# BW1097_Power_Supply.net
KiCad netlist of a schematic drawn in Altium Designer
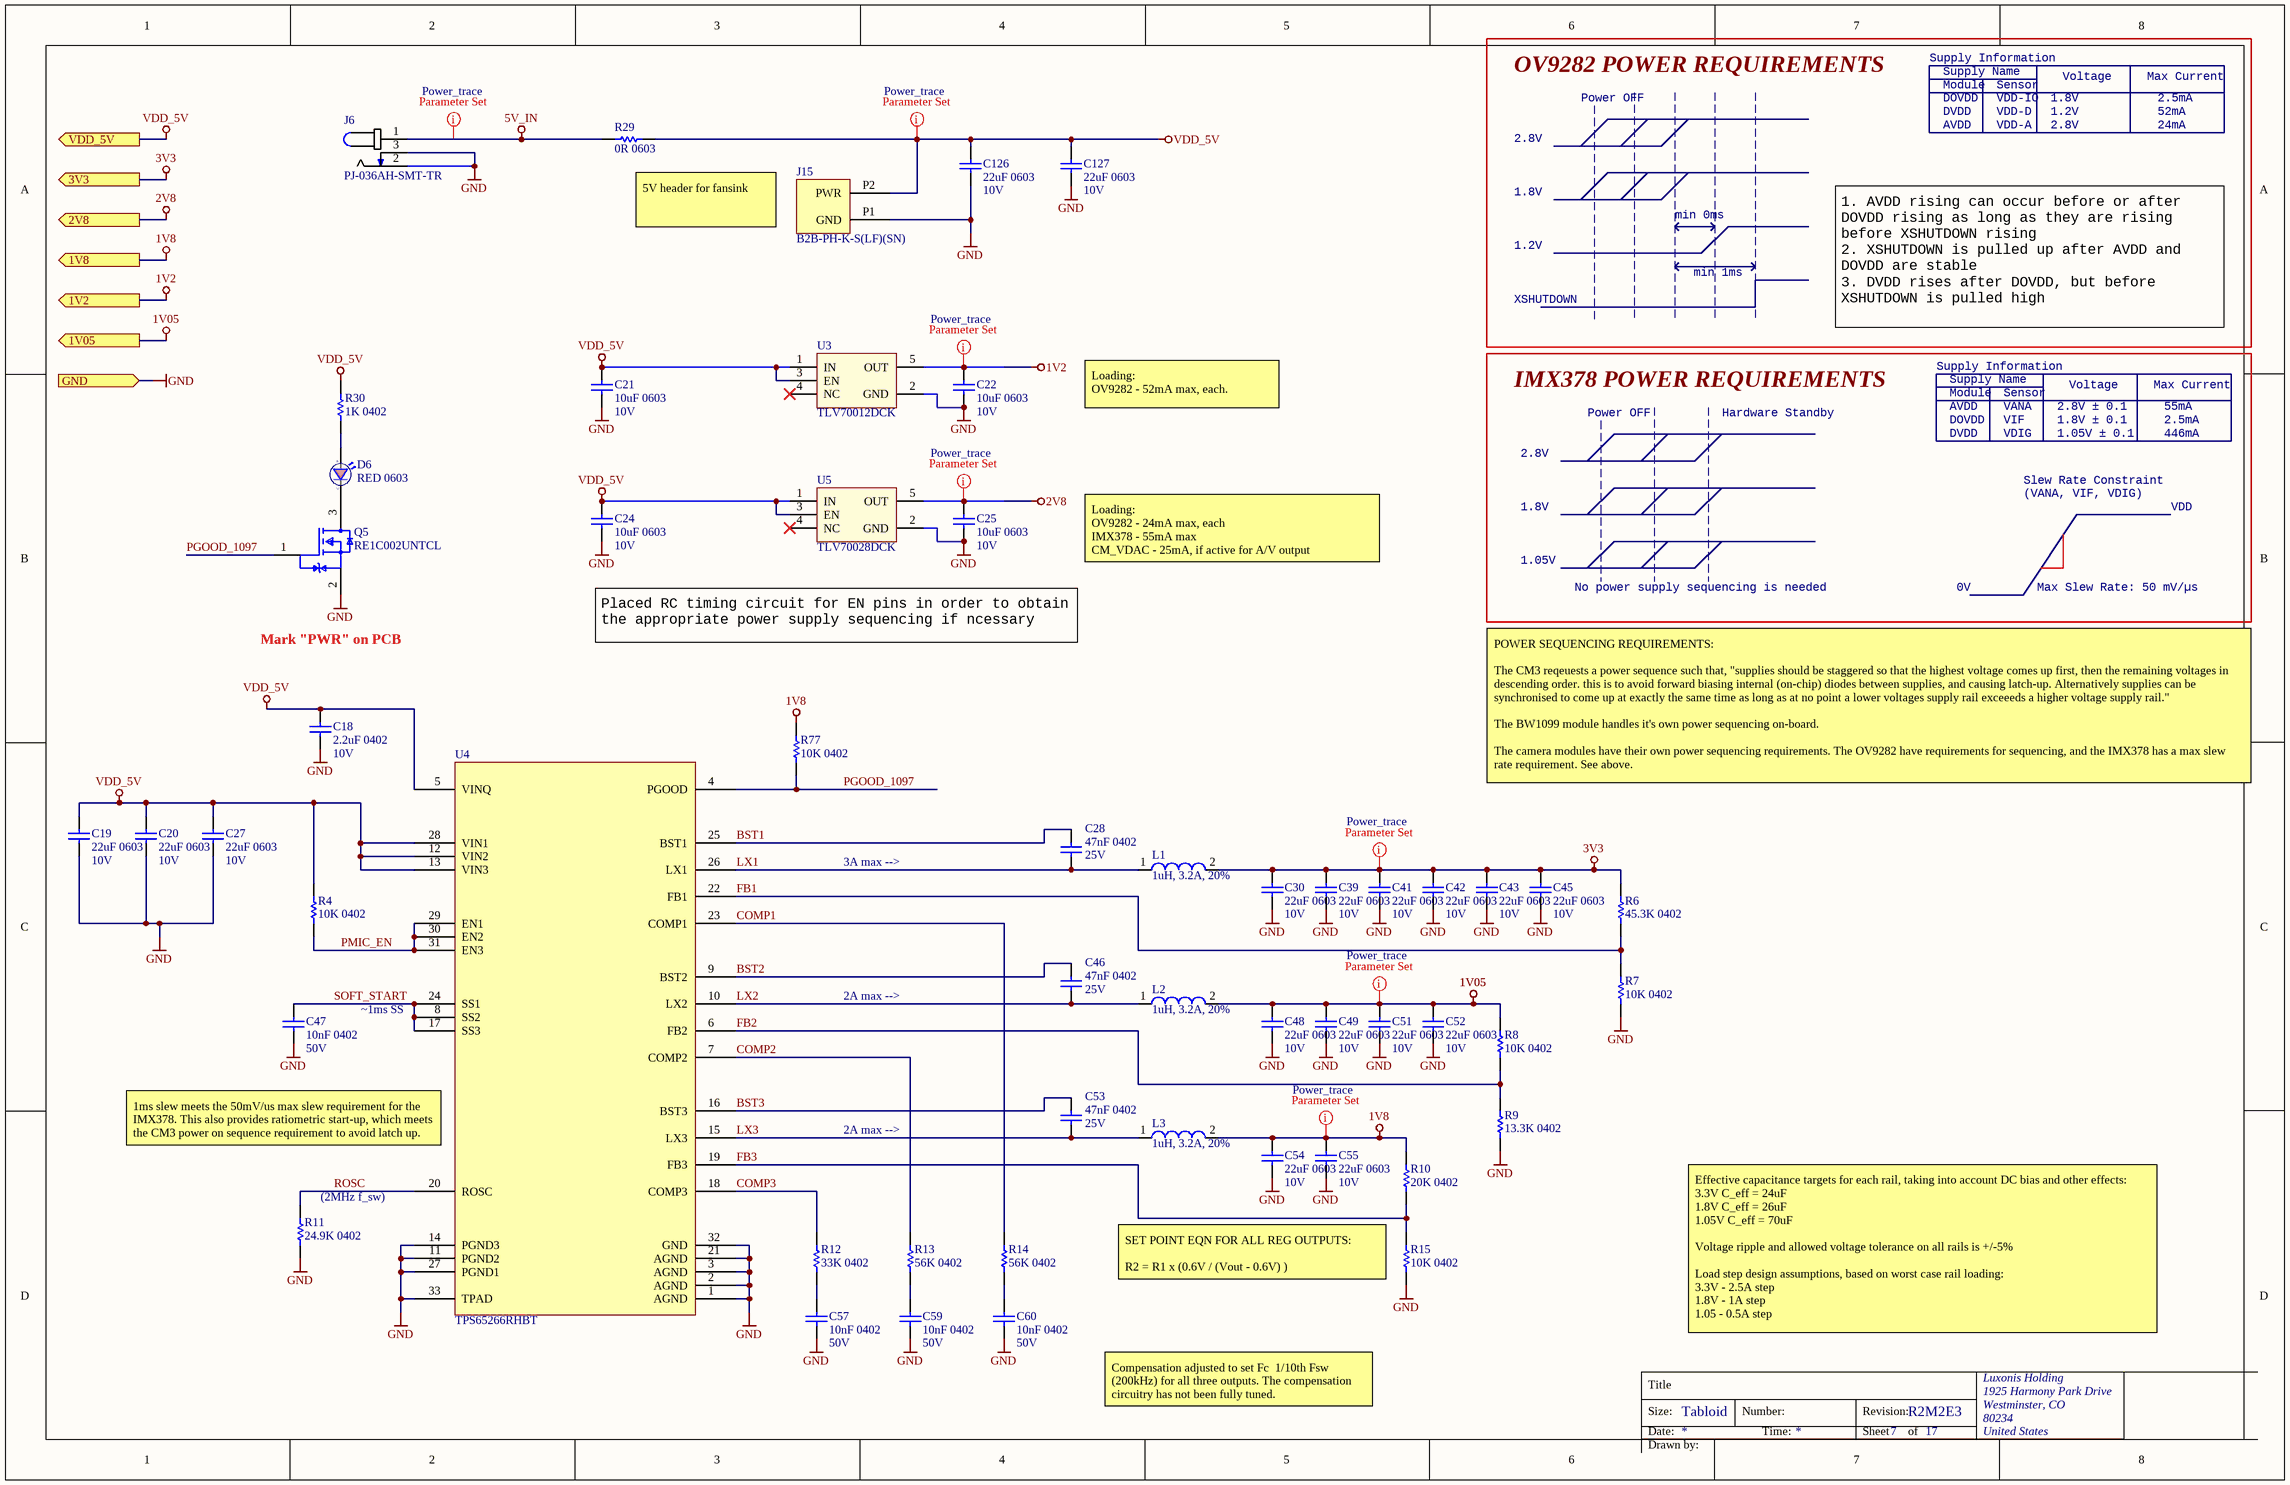
[diagram p0: BW1097_Power_Supply.SchDoc]

(export (version "E")
  (design (tool "Eeschema 10.0.6"))
  (components
    (comp (ref "C18")
      (value "2.2uF 0402")
      (footprint "CAP_Altium_Vault_Generic:CAPC0402(1005)70_N")
      (description "CAP CER 2.2UF 10V X5R 0402 10%")
      (fields (field (name "TOLERANCE") "10%") (field (name "VOLTAGE RATING") "10V"))
      (libsource (lib "LuxonisMaster") (part "GRM155R61A225KE95D"))
    )
    (comp (ref "C19")
      (value "22uF 0603")
      (footprint "CAP_Altium_Vault_Generic:CAPC0603(1608)100_N")
      (description "CAP CER 22UF 10V X5R 0603 20%")
      (fields (field (name "TOLERANCE") "20%") (field (name "VOLTAGE RATING") "10V"))
      (libsource (lib "LuxonisMaster") (part "GRM188R61A226ME15D"))
    )
    (comp (ref "C20")
      (value "22uF 0603")
      (footprint "CAP_Altium_Vault_Generic:CAPC0603(1608)100_N")
      (description "CAP CER 22UF 10V X5R 0603 20%")
      (fields (field (name "TOLERANCE") "20%") (field (name "VOLTAGE RATING") "10V"))
      (libsource (lib "LuxonisMaster") (part "GRM188R61A226ME15D"))
    )
    (comp (ref "C21")
      (value "10uF 0603")
      (footprint "CAP_Altium_Vault_Generic:CAPC0603(1608)100_N")
      (description "CAP CER 10UF 10V X5R 0603 20%")
      (fields (field (name "TOLERANCE") "20%") (field (name "VOLTAGE RATING") "10V"))
      (libsource (lib "LuxonisMaster") (part "GRM188R61A106ME69D"))
    )
    (comp (ref "C22")
      (value "10uF 0603")
      (footprint "CAP_Altium_Vault_Generic:CAPC0603(1608)100_N")
      (description "CAP CER 10UF 10V X5R 0603 20%")
      (fields (field (name "TOLERANCE") "20%") (field (name "VOLTAGE RATING") "10V"))
      (libsource (lib "LuxonisMaster") (part "GRM188R61A106ME69D"))
    )
    (comp (ref "C24")
      (value "10uF 0603")
      (footprint "CAP_Altium_Vault_Generic:CAPC0603(1608)100_N")
      (description "CAP CER 10UF 10V X5R 0603 20%")
      (fields (field (name "TOLERANCE") "20%") (field (name "VOLTAGE RATING") "10V"))
      (libsource (lib "LuxonisMaster") (part "GRM188R61A106ME69D"))
    )
    (comp (ref "C25")
      (value "10uF 0603")
      (footprint "CAP_Altium_Vault_Generic:CAPC0603(1608)100_N")
      (description "CAP CER 10UF 10V X5R 0603 20%")
      (fields (field (name "TOLERANCE") "20%") (field (name "VOLTAGE RATING") "10V"))
      (libsource (lib "LuxonisMaster") (part "GRM188R61A106ME69D"))
    )
    (comp (ref "C27")
      (value "22uF 0603")
      (footprint "CAP_Altium_Vault_Generic:CAPC0603(1608)100_N")
      (description "CAP CER 22UF 10V X5R 0603 20%")
      (fields (field (name "TOLERANCE") "20%") (field (name "VOLTAGE RATING") "10V"))
      (libsource (lib "LuxonisMaster") (part "GRM188R61A226ME15D"))
    )
    (comp (ref "C28")
      (value "47nF 0402")
      (footprint "CAP_Altium_Vault_Generic:CAPC0402(1005)70_N")
      (description "CAP CER 0.047UF 25V X7R 0402 10%")
      (fields
        (field (name "MANUFACTURER") "Murata")
        (field (name "MANUFACTURER PART NUMBER") "GRM155R71E473KA88D")
        (field (name "VOLTAGE") "25V")
      )
      (libsource (lib "LuxonisMaster") (part "GRM155R71E473KA88D"))
    )
    (comp (ref "C30")
      (value "22uF 0603")
      (footprint "CAP_Altium_Vault_Generic:CAPC0603(1608)100_N")
      (description "CAP CER 22UF 10V X5R 0603 20%")
      (fields (field (name "TOLERANCE") "20%") (field (name "VOLTAGE RATING") "10V"))
      (libsource (lib "LuxonisMaster") (part "GRM188R61A226ME15D"))
    )
    (comp (ref "C39")
      (value "22uF 0603")
      (footprint "CAP_Altium_Vault_Generic:CAPC0603(1608)100_N")
      (description "CAP CER 22UF 10V X5R 0603 20%")
      (fields (field (name "TOLERANCE") "20%") (field (name "VOLTAGE RATING") "10V"))
      (libsource (lib "LuxonisMaster") (part "GRM188R61A226ME15D"))
    )
    (comp (ref "C41")
      (value "22uF 0603")
      (footprint "CAP_Altium_Vault_Generic:CAPC0603(1608)100_N")
      (description "CAP CER 22UF 10V X5R 0603 20%")
      (fields (field (name "TOLERANCE") "20%") (field (name "VOLTAGE RATING") "10V"))
      (libsource (lib "LuxonisMaster") (part "GRM188R61A226ME15D"))
    )
    (comp (ref "C42")
      (value "22uF 0603")
      (footprint "CAP_Altium_Vault_Generic:CAPC0603(1608)100_N")
      (description "CAP CER 22UF 10V X5R 0603 20%")
      (fields (field (name "TOLERANCE") "20%") (field (name "VOLTAGE RATING") "10V"))
      (libsource (lib "LuxonisMaster") (part "GRM188R61A226ME15D"))
    )
    (comp (ref "C43")
      (value "22uF 0603")
      (footprint "CAP_Altium_Vault_Generic:CAPC0603(1608)100_N")
      (description "CAP CER 22UF 10V X5R 0603 20%")
      (fields (field (name "TOLERANCE") "20%") (field (name "VOLTAGE RATING") "10V"))
      (libsource (lib "LuxonisMaster") (part "GRM188R61A226ME15D"))
    )
    (comp (ref "C45")
      (value "22uF 0603")
      (footprint "CAP_Altium_Vault_Generic:CAPC0603(1608)100_N")
      (description "CAP CER 22UF 10V X5R 0603 20%")
      (fields (field (name "TOLERANCE") "20%") (field (name "VOLTAGE RATING") "10V"))
      (libsource (lib "LuxonisMaster") (part "GRM188R61A226ME15D"))
    )
    (comp (ref "C46")
      (value "47nF 0402")
      (footprint "CAP_Altium_Vault_Generic:CAPC0402(1005)70_N")
      (description "CAP CER 0.047UF 25V X7R 0402 10%")
      (fields
        (field (name "MANUFACTURER") "Murata")
        (field (name "MANUFACTURER PART NUMBER") "GRM155R71E473KA88D")
        (field (name "VOLTAGE") "25V")
      )
      (libsource (lib "LuxonisMaster") (part "GRM155R71E473KA88D"))
    )
    (comp (ref "C47")
      (value "10nF 0402")
      (footprint "CAP_Altium_Vault_Generic:CAPC0402(1005)60_N")
      (description "CAP CER 10000PF 50V X7R 0402")
      (fields
        (field (name "TOLERANCE") "10%")
        (field (name "VOLTAGE") "25V")
        (field (name "VOLTAGE RATING") "50V")
      )
      (libsource (lib "LuxonisMaster") (part "GRM155R71H103KA88D"))
    )
    (comp (ref "C48")
      (value "22uF 0603")
      (footprint "CAP_Altium_Vault_Generic:CAPC0603(1608)100_N")
      (description "CAP CER 22UF 10V X5R 0603 20%")
      (fields (field (name "TOLERANCE") "20%") (field (name "VOLTAGE RATING") "10V"))
      (libsource (lib "LuxonisMaster") (part "GRM188R61A226ME15D"))
    )
    (comp (ref "C49")
      (value "22uF 0603")
      (footprint "CAP_Altium_Vault_Generic:CAPC0603(1608)100_N")
      (description "CAP CER 22UF 10V X5R 0603 20%")
      (fields (field (name "TOLERANCE") "20%") (field (name "VOLTAGE RATING") "10V"))
      (libsource (lib "LuxonisMaster") (part "GRM188R61A226ME15D"))
    )
    (comp (ref "C51")
      (value "22uF 0603")
      (footprint "CAP_Altium_Vault_Generic:CAPC0603(1608)100_N")
      (description "CAP CER 22UF 10V X5R 0603 20%")
      (fields (field (name "TOLERANCE") "20%") (field (name "VOLTAGE RATING") "10V"))
      (libsource (lib "LuxonisMaster") (part "GRM188R61A226ME15D"))
    )
    (comp (ref "C52")
      (value "22uF 0603")
      (footprint "CAP_Altium_Vault_Generic:CAPC0603(1608)100_N")
      (description "CAP CER 22UF 10V X5R 0603 20%")
      (fields (field (name "TOLERANCE") "20%") (field (name "VOLTAGE RATING") "10V"))
      (libsource (lib "LuxonisMaster") (part "GRM188R61A226ME15D"))
    )
    (comp (ref "C53")
      (value "47nF 0402")
      (footprint "CAP_Altium_Vault_Generic:CAPC0402(1005)70_N")
      (description "CAP CER 0.047UF 25V X7R 0402 10%")
      (fields
        (field (name "MANUFACTURER") "Murata")
        (field (name "MANUFACTURER PART NUMBER") "GRM155R71E473KA88D")
        (field (name "VOLTAGE") "25V")
      )
      (libsource (lib "LuxonisMaster") (part "GRM155R71E473KA88D"))
    )
    (comp (ref "C54")
      (value "22uF 0603")
      (footprint "CAP_Altium_Vault_Generic:CAPC0603(1608)100_N")
      (description "CAP CER 22UF 10V X5R 0603 20%")
      (fields (field (name "TOLERANCE") "20%") (field (name "VOLTAGE RATING") "10V"))
      (libsource (lib "LuxonisMaster") (part "GRM188R61A226ME15D"))
    )
    (comp (ref "C55")
      (value "22uF 0603")
      (footprint "CAP_Altium_Vault_Generic:CAPC0603(1608)100_N")
      (description "CAP CER 22UF 10V X5R 0603 20%")
      (fields (field (name "TOLERANCE") "20%") (field (name "VOLTAGE RATING") "10V"))
      (libsource (lib "LuxonisMaster") (part "GRM188R61A226ME15D"))
    )
    (comp (ref "C57")
      (value "10nF 0402")
      (footprint "CAP_Altium_Vault_Generic:CAPC0402(1005)60_N")
      (description "CAP CER 10000PF 50V X7R 0402")
      (fields
        (field (name "TOLERANCE") "10%")
        (field (name "VOLTAGE") "25V")
        (field (name "VOLTAGE RATING") "50V")
      )
      (libsource (lib "LuxonisMaster") (part "GRM155R71H103KA88D"))
    )
    (comp (ref "C59")
      (value "10nF 0402")
      (footprint "CAP_Altium_Vault_Generic:CAPC0402(1005)60_N")
      (description "CAP CER 10000PF 50V X7R 0402")
      (fields
        (field (name "TOLERANCE") "10%")
        (field (name "VOLTAGE") "25V")
        (field (name "VOLTAGE RATING") "50V")
      )
      (libsource (lib "LuxonisMaster") (part "GRM155R71H103KA88D"))
    )
    (comp (ref "C60")
      (value "10nF 0402")
      (footprint "CAP_Altium_Vault_Generic:CAPC0402(1005)60_N")
      (description "CAP CER 10000PF 50V X7R 0402")
      (fields
        (field (name "TOLERANCE") "10%")
        (field (name "VOLTAGE") "25V")
        (field (name "VOLTAGE RATING") "50V")
      )
      (libsource (lib "LuxonisMaster") (part "GRM155R71H103KA88D"))
    )
    (comp (ref "C126")
      (value "22uF 0603")
      (footprint "CAP_Altium_Vault_Generic:CAPC0603(1608)100_N")
      (description "CAP CER 22UF 10V X5R 0603 20%")
      (fields (field (name "TOLERANCE") "20%") (field (name "VOLTAGE RATING") "10V"))
      (libsource (lib "LuxonisMaster") (part "GRM188R61A226ME15D"))
    )
    (comp (ref "C127")
      (value "22uF 0603")
      (footprint "CAP_Altium_Vault_Generic:CAPC0603(1608)100_N")
      (description "CAP CER 22UF 10V X5R 0603 20%")
      (fields (field (name "TOLERANCE") "20%") (field (name "VOLTAGE RATING") "10V"))
      (libsource (lib "LuxonisMaster") (part "GRM188R61A226ME15D"))
    )
    (comp (ref "D6")
      (value "RED 0603")
      (footprint "LuxonisMaster:SML_D1xx8W")
      (description "LED RED DIFFUSED 0603 SMD Red 620nm LED Indication - Discrete 2.2V 0603 (1608 Metric)")
      (libsource (lib "LuxonisMaster") (part "SML-D12U8WT86"))
    )
    (comp (ref "J6")
      (value "PJ-036AH-SMT-TR")
      (footprint "LuxonisMaster:PJ-036AH-SMT")
      (description "CONN PWR JACK 2X5.5MM SOLDER")
      (libsource (lib "LuxonisMaster") (part "PJ-036AH-SMT-TR"))
    )
    (comp (ref "J15")
      (value "B2B-PH-K-S(LF)(SN)")
      (footprint "LuxonisMaster:B2B-PH-K-S(LF)(SN)")
      (description "CONN HEADER VERT 2POS 2MM")
      (libsource (lib "LuxonisMaster") (part "B2B-PH-K-S(LF)(SN)"))
    )
    (comp (ref "L1")
      (value "1uH, 3.2A, 20%")
      (footprint "LuxonisMaster:DFE252012P-1R0M=P2")
      (description "FIXED IND 1UH 3.2A 42 MOHM SMD")
      (fields
        (field (name "MANUFACTURER") "Murata")
        (field (name "MANUFACTURER PART NUMBER") "DFE252012P-1R0M=P2")
      )
      (libsource (lib "LuxonisMaster") (part "DFE252012P-1R0M=P2"))
    )
    (comp (ref "L2")
      (value "1uH, 3.2A, 20%")
      (footprint "LuxonisMaster:DFE252012P-1R0M=P2")
      (description "FIXED IND 1UH 3.2A 42 MOHM SMD")
      (fields
        (field (name "MANUFACTURER") "Murata")
        (field (name "MANUFACTURER PART NUMBER") "DFE252012P-1R0M=P2")
      )
      (libsource (lib "LuxonisMaster") (part "DFE252012P-1R0M=P2"))
    )
    (comp (ref "L3")
      (value "1uH, 3.2A, 20%")
      (footprint "LuxonisMaster:DFE252012P-1R0M=P2")
      (description "FIXED IND 1UH 3.2A 42 MOHM SMD")
      (fields
        (field (name "MANUFACTURER") "Murata")
        (field (name "MANUFACTURER PART NUMBER") "DFE252012P-1R0M=P2")
      )
      (libsource (lib "LuxonisMaster") (part "DFE252012P-1R0M=P2"))
    )
    (comp (ref "Q5")
      (value "RE1C002UNTCL")
      (footprint "LuxonisMaster:RE1C002UNTCL")
      (description "MOSFET N-CH 20V 0.2A EMT3")
      (libsource (lib "LuxonisMaster") (part "RE1C002UNTCL"))
    )
    (comp (ref "R4")
      (value "10K 0402")
      (footprint "RES_Altium_Vault_Generic:RESC0402(1005)_N")
      (fields (field (name "TOLERANCE") "1%"))
      (libsource (lib "LuxonisMaster") (part "RC0402FR-1310KL"))
    )
    (comp (ref "R6")
      (value "45.3K 0402")
      (footprint "RES_Altium_Vault_Generic:RESC0402(1005)_N")
      (description "RES SMD 45.3K OHM 1% 1/16W 0402")
      (fields (field (name "TOLERANCE") "1%"))
      (libsource (lib "LuxonisMaster") (part "RC0402FR-0745K3L"))
    )
    (comp (ref "R7")
      (value "10K 0402")
      (footprint "RES_Altium_Vault_Generic:RESC0402(1005)_N")
      (fields (field (name "TOLERANCE") "1%"))
      (libsource (lib "LuxonisMaster") (part "RC0402FR-1310KL"))
    )
    (comp (ref "R8")
      (value "10K 0402")
      (footprint "RES_Altium_Vault_Generic:RESC0402(1005)_N")
      (fields (field (name "TOLERANCE") "1%"))
      (libsource (lib "LuxonisMaster") (part "RC0402FR-1310KL"))
    )
    (comp (ref "R9")
      (value "13.3K 0402")
      (footprint "RES_Altium_Vault_Generic:RESC0402(1005)_N")
      (description "RES SMD 13.3K OHM 1% 1/16W 0402")
      (fields (field (name "TOLERANCE") "1%"))
      (libsource (lib "LuxonisMaster") (part "RC0402FR-0713K3L"))
    )
    (comp (ref "R10")
      (value "20K 0402")
      (footprint "RES_Altium_Vault_Generic:RESC0402(1005)_N")
      (fields
        (field (name "MANUFACTURER") "Yageo")
        (field (name "MANUFACTURER PART NUMBER") "RC0402FR-0720KL")
        (field (name "TOLERANCE") "1%")
      )
      (libsource (lib "LuxonisMaster") (part "RC0402FR-0720KL"))
    )
    (comp (ref "R11")
      (value "24.9K 0402")
      (footprint "RES_Altium_Vault_Generic:RESC0402(1005)_N")
      (description "RES SMD 24.9K OHM 1% 1/16W 0402")
      (fields (field (name "TOLERANCE") "1%"))
      (libsource (lib "LuxonisMaster") (part "RC0402FR-0724K9L"))
    )
    (comp (ref "R12")
      (value "33K 0402")
      (footprint "RES_Altium_Vault_Generic:RESC0402(1005)_N")
      (description "RES SMD 33K OHM 1% 1/16W 0402")
      (fields (field (name "TOLERANCE") "1%"))
      (libsource (lib "LuxonisMaster") (part "CRCW040233K0FKED"))
    )
    (comp (ref "R13")
      (value "56K 0402")
      (footprint "RES_Altium_Vault_Generic:RESC0402(1005)_N")
      (fields
        (field (name "MANUFACTURER") "Yageo")
        (field (name "MANUFACTURER PART NUMBER") "RC0402FR-0756KL")
        (field (name "TOLERANCE") "1%")
      )
      (libsource (lib "LuxonisMaster") (part "RC0402FR-0756KL"))
    )
    (comp (ref "R14")
      (value "56K 0402")
      (footprint "RES_Altium_Vault_Generic:RESC0402(1005)_N")
      (fields
        (field (name "MANUFACTURER") "Yageo")
        (field (name "MANUFACTURER PART NUMBER") "RC0402FR-0756KL")
        (field (name "TOLERANCE") "1%")
      )
      (libsource (lib "LuxonisMaster") (part "RC0402FR-0756KL"))
    )
    (comp (ref "R15")
      (value "10K 0402")
      (footprint "RES_Altium_Vault_Generic:RESC0402(1005)_N")
      (fields (field (name "TOLERANCE") "1%"))
      (libsource (lib "LuxonisMaster") (part "RC0402FR-1310KL"))
    )
    (comp (ref "R29")
      (value "0R 0603")
      (footprint "RES_Altium_Vault_Generic:RESC0603(1608)_N")
      (fields (field (name "TOLERANCE") "5%"))
      (libsource (lib "LuxonisMaster") (part "CRCW06030000Z0EA"))
    )
    (comp (ref "R30")
      (value "1K 0402")
      (footprint "RES_Altium_Vault_Generic:RESC0402(1005)_N")
      (fields (field (name "TOLERANCE") "1%"))
      (libsource (lib "LuxonisMaster") (part "RC0402FR-071KL"))
    )
    (comp (ref "R77")
      (value "10K 0402")
      (footprint "RES_Altium_Vault_Generic:RESC0402(1005)_N")
      (fields (field (name "TOLERANCE") "1%"))
      (libsource (lib "LuxonisMaster") (part "RC0402FR-1310KL"))
    )
    (comp (ref "U3")
      (value "TLV70012DCK")
      (footprint "LuxonisMaster:TLV70012DCK")
      (description "IC REG LINEAR 1.2V 200MA SC70-5")
      (libsource (lib "LuxonisMaster") (part "TLV70012DCK"))
    )
    (comp (ref "U4")
      (value "TPS65266RHBT")
      (footprint "LuxonisMaster:TPS65266RHBT")
      (fields (field (name "MANUFACTURER") "TI"))
      (libsource (lib "LuxonisMaster") (part "TPS65266RHBT"))
    )
    (comp (ref "U5")
      (value "TLV70028DCK")
      (footprint "LuxonisMaster:TLV70028DCK")
      (description "IC REG LINEAR 2.8V 200MA SC70-5 Linear Voltage Regulator IC  1 Output  200mA SC-70-5")
      (libsource (lib "LuxonisMaster") (part "TLV70028DCK"))
    )
  )
  (nets
    (net (code "1") (name "/BST1") (class "Default")
      (node (ref "C28") (pin "1") (pinfunction "1_1") (pintype "passive"))
      (node (ref "U4") (pin "25") (pinfunction "BST1_25") (pintype "passive"))
    )
    (net (code "2") (name "/BST2") (class "Default")
      (node (ref "C46") (pin "1") (pinfunction "1_1") (pintype "passive"))
      (node (ref "U4") (pin "9") (pinfunction "BST2_9") (pintype "passive"))
    )
    (net (code "3") (name "/BST3") (class "Default")
      (node (ref "C53") (pin "1") (pinfunction "1_1") (pintype "passive"))
      (node (ref "U4") (pin "16") (pinfunction "BST3_16") (pintype "passive"))
    )
    (net (code "4") (name "/COMP1") (class "Default")
      (node (ref "R14") (pin "2") (pinfunction "2_2") (pintype "passive"))
      (node (ref "U4") (pin "23") (pinfunction "COMP1_23") (pintype "passive"))
    )
    (net (code "5") (name "/COMP2") (class "Default")
      (node (ref "R13") (pin "2") (pinfunction "2_2") (pintype "passive"))
      (node (ref "U4") (pin "7") (pinfunction "COMP2_7") (pintype "passive"))
    )
    (net (code "6") (name "/COMP3") (class "Default")
      (node (ref "R12") (pin "2") (pinfunction "2_2") (pintype "passive"))
      (node (ref "U4") (pin "18") (pinfunction "COMP3_18") (pintype "passive"))
    )
    (net (code "7") (name "/FB1") (class "Default")
      (node (ref "R6") (pin "1") (pinfunction "1_1") (pintype "passive"))
      (node (ref "R7") (pin "2") (pinfunction "2_2") (pintype "passive"))
      (node (ref "U4") (pin "22") (pinfunction "FB1_22") (pintype "passive"))
    )
    (net (code "8") (name "/FB2") (class "Default")
      (node (ref "R8") (pin "1") (pinfunction "1_1") (pintype "passive"))
      (node (ref "R9") (pin "2") (pinfunction "2_2") (pintype "passive"))
      (node (ref "U4") (pin "6") (pinfunction "FB2_6") (pintype "passive"))
    )
    (net (code "9") (name "/FB3") (class "Default")
      (node (ref "R10") (pin "1") (pinfunction "1_1") (pintype "passive"))
      (node (ref "R15") (pin "2") (pinfunction "2_2") (pintype "passive"))
      (node (ref "U4") (pin "19") (pinfunction "FB3_19") (pintype "passive"))
    )
    (net (code "10") (name "/LX1") (class "Default")
      (node (ref "C28") (pin "2") (pinfunction "2_2") (pintype "passive"))
      (node (ref "L1") (pin "1") (pinfunction "1_1") (pintype "passive"))
      (node (ref "U4") (pin "26") (pinfunction "LX1_26") (pintype "passive"))
    )
    (net (code "11") (name "/LX2") (class "Default")
      (node (ref "C46") (pin "2") (pinfunction "2_2") (pintype "passive"))
      (node (ref "L2") (pin "1") (pinfunction "1_1") (pintype "passive"))
      (node (ref "U4") (pin "10") (pinfunction "LX2_10") (pintype "passive"))
    )
    (net (code "12") (name "/LX3") (class "Default")
      (node (ref "C53") (pin "2") (pinfunction "2_2") (pintype "passive"))
      (node (ref "L3") (pin "1") (pinfunction "1_1") (pintype "passive"))
      (node (ref "U4") (pin "15") (pinfunction "LX3_15") (pintype "passive"))
    )
    (net (code "13") (name "/PGOOD_1097") (class "Default")
      (node (ref "Q5") (pin "1") (pinfunction "Gate_1") (pintype "passive"))
      (node (ref "R77") (pin "1") (pinfunction "1_1") (pintype "passive"))
      (node (ref "U4") (pin "4") (pinfunction "PGOOD_4") (pintype "passive"))
    )
    (net (code "14") (name "/PMIC_EN") (class "Default")
      (node (ref "R4") (pin "1") (pinfunction "1_1") (pintype "passive"))
      (node (ref "U4") (pin "29") (pinfunction "EN1_29") (pintype "passive"))
      (node (ref "U4") (pin "30") (pinfunction "EN2_30") (pintype "passive"))
      (node (ref "U4") (pin "31") (pinfunction "EN3_31") (pintype "passive"))
    )
    (net (code "15") (name "/ROSC") (class "Default")
      (node (ref "R11") (pin "2") (pinfunction "2_2") (pintype "passive"))
      (node (ref "U4") (pin "20") (pinfunction "ROSC_20") (pintype "passive"))
    )
    (net (code "16") (name "/SOFT_START") (class "Default")
      (node (ref "C47") (pin "1") (pinfunction "1_1") (pintype "passive"))
      (node (ref "U4") (pin "17") (pinfunction "SS3_17") (pintype "passive"))
      (node (ref "U4") (pin "24") (pinfunction "SS1_24") (pintype "passive"))
      (node (ref "U4") (pin "8") (pinfunction "SS2_8") (pintype "passive"))
    )
    (net (code "17") (name "1V2") (class "Default")
      (node (ref "C22") (pin "2") (pinfunction "2_2") (pintype "passive"))
      (node (ref "U3") (pin "5") (pinfunction "OUT_5") (pintype "passive"))
    )
    (net (code "18") (name "1V05") (class "Default")
      (node (ref "C48") (pin "1") (pinfunction "1_1") (pintype "passive"))
      (node (ref "C49") (pin "1") (pinfunction "1_1") (pintype "passive"))
      (node (ref "C51") (pin "1") (pinfunction "1_1") (pintype "passive"))
      (node (ref "C52") (pin "1") (pinfunction "1_1") (pintype "passive"))
      (node (ref "L2") (pin "2") (pinfunction "2_2") (pintype "passive"))
      (node (ref "R8") (pin "2") (pinfunction "2_2") (pintype "passive"))
    )
    (net (code "19") (name "1V8") (class "Default")
      (node (ref "C54") (pin "1") (pinfunction "1_1") (pintype "passive"))
      (node (ref "C55") (pin "1") (pinfunction "1_1") (pintype "passive"))
      (node (ref "L3") (pin "2") (pinfunction "2_2") (pintype "passive"))
      (node (ref "R10") (pin "2") (pinfunction "2_2") (pintype "passive"))
      (node (ref "R77") (pin "2") (pinfunction "2_2") (pintype "passive"))
    )
    (net (code "20") (name "2V8") (class "Default")
      (node (ref "C25") (pin "2") (pinfunction "2_2") (pintype "passive"))
      (node (ref "U5") (pin "5") (pinfunction "OUT_5") (pintype "passive"))
    )
    (net (code "21") (name "3V3") (class "Default")
      (node (ref "C30") (pin "1") (pinfunction "1_1") (pintype "passive"))
      (node (ref "C39") (pin "1") (pinfunction "1_1") (pintype "passive"))
      (node (ref "C41") (pin "1") (pinfunction "1_1") (pintype "passive"))
      (node (ref "C42") (pin "1") (pinfunction "1_1") (pintype "passive"))
      (node (ref "C43") (pin "1") (pinfunction "1_1") (pintype "passive"))
      (node (ref "C45") (pin "1") (pinfunction "1_1") (pintype "passive"))
      (node (ref "L1") (pin "2") (pinfunction "2_2") (pintype "passive"))
      (node (ref "R6") (pin "2") (pinfunction "2_2") (pintype "passive"))
    )
    (net (code "22") (name "5V_IN") (class "Default")
      (node (ref "J6") (pin "1") (pinfunction "1_1") (pintype "passive"))
      (node (ref "R29") (pin "2") (pinfunction "2_2") (pintype "passive"))
    )
    (net (code "23") (name "GND") (class "Default")
      (node (ref "C126") (pin "2") (pinfunction "2_2") (pintype "passive"))
      (node (ref "C127") (pin "2") (pinfunction "2_2") (pintype "passive"))
      (node (ref "C18") (pin "2") (pinfunction "2_2") (pintype "passive"))
      (node (ref "C19") (pin "2") (pinfunction "2_2") (pintype "passive"))
      (node (ref "C20") (pin "2") (pinfunction "2_2") (pintype "passive"))
      (node (ref "C21") (pin "1") (pinfunction "1_1") (pintype "passive"))
      (node (ref "C22") (pin "1") (pinfunction "1_1") (pintype "passive"))
      (node (ref "C24") (pin "1") (pinfunction "1_1") (pintype "passive"))
      (node (ref "C25") (pin "1") (pinfunction "1_1") (pintype "passive"))
      (node (ref "C27") (pin "2") (pinfunction "2_2") (pintype "passive"))
      (node (ref "C30") (pin "2") (pinfunction "2_2") (pintype "passive"))
      (node (ref "C39") (pin "2") (pinfunction "2_2") (pintype "passive"))
      (node (ref "C41") (pin "2") (pinfunction "2_2") (pintype "passive"))
      (node (ref "C42") (pin "2") (pinfunction "2_2") (pintype "passive"))
      (node (ref "C43") (pin "2") (pinfunction "2_2") (pintype "passive"))
      (node (ref "C45") (pin "2") (pinfunction "2_2") (pintype "passive"))
      (node (ref "C47") (pin "2") (pinfunction "2_2") (pintype "passive"))
      (node (ref "C48") (pin "2") (pinfunction "2_2") (pintype "passive"))
      (node (ref "C49") (pin "2") (pinfunction "2_2") (pintype "passive"))
      (node (ref "C51") (pin "2") (pinfunction "2_2") (pintype "passive"))
      (node (ref "C52") (pin "2") (pinfunction "2_2") (pintype "passive"))
      (node (ref "C54") (pin "2") (pinfunction "2_2") (pintype "passive"))
      (node (ref "C55") (pin "2") (pinfunction "2_2") (pintype "passive"))
      (node (ref "C57") (pin "2") (pinfunction "2_2") (pintype "passive"))
      (node (ref "C59") (pin "2") (pinfunction "2_2") (pintype "passive"))
      (node (ref "C60") (pin "2") (pinfunction "2_2") (pintype "passive"))
      (node (ref "J15") (pin "P1") (pinfunction "GND_P1") (pintype "passive"))
      (node (ref "J6") (pin "2") (pinfunction "2_2") (pintype "passive"))
      (node (ref "J6") (pin "3") (pinfunction "3_3") (pintype "passive"))
      (node (ref "Q5") (pin "2") (pinfunction "Source_2") (pintype "passive"))
      (node (ref "R11") (pin "1") (pinfunction "1_1") (pintype "passive"))
      (node (ref "R15") (pin "1") (pinfunction "1_1") (pintype "passive"))
      (node (ref "R7") (pin "1") (pinfunction "1_1") (pintype "passive"))
      (node (ref "R9") (pin "1") (pinfunction "1_1") (pintype "passive"))
      (node (ref "U3") (pin "2") (pinfunction "GND_2") (pintype "passive"))
      (node (ref "U4") (pin "1") (pinfunction "AGND_1") (pintype "passive"))
      (node (ref "U4") (pin "11") (pinfunction "PGND2_11") (pintype "passive"))
      (node (ref "U4") (pin "14") (pinfunction "PGND3_14") (pintype "passive"))
      (node (ref "U4") (pin "2") (pinfunction "AGND_2") (pintype "passive"))
      (node (ref "U4") (pin "21") (pinfunction "AGND_21") (pintype "passive"))
      (node (ref "U4") (pin "27") (pinfunction "PGND1_27") (pintype "passive"))
      (node (ref "U4") (pin "3") (pinfunction "AGND_3") (pintype "passive"))
      (node (ref "U4") (pin "32") (pinfunction "GND_32") (pintype "passive"))
      (node (ref "U4") (pin "33") (pinfunction "TPAD_33") (pintype "passive"))
      (node (ref "U5") (pin "2") (pinfunction "GND_2") (pintype "passive"))
    )
    (net (code "24") (name "Net-(C57-Pad1)") (class "Default")
      (node (ref "C57") (pin "1") (pinfunction "1_1") (pintype "passive"))
      (node (ref "R12") (pin "1") (pinfunction "1_1") (pintype "passive"))
    )
    (net (code "25") (name "Net-(C59-Pad1)") (class "Default")
      (node (ref "C59") (pin "1") (pinfunction "1_1") (pintype "passive"))
      (node (ref "R13") (pin "1") (pinfunction "1_1") (pintype "passive"))
    )
    (net (code "26") (name "Net-(C60-Pad1)") (class "Default")
      (node (ref "C60") (pin "1") (pinfunction "1_1") (pintype "passive"))
      (node (ref "R14") (pin "1") (pinfunction "1_1") (pintype "passive"))
    )
    (net (code "27") (name "Net-(D6-A)") (class "Default")
      (node (ref "D6") (pin "2") (pinfunction "A_2") (pintype "passive"))
      (node (ref "R30") (pin "1") (pinfunction "1_1") (pintype "passive"))
    )
    (net (code "28") (name "Net-(D6-C)") (class "Default")
      (node (ref "D6") (pin "1") (pinfunction "C_1") (pintype "passive"))
      (node (ref "Q5") (pin "3") (pinfunction "Drain_3") (pintype "passive"))
    )
    (net (code "29") (name "VDD_5V") (class "Default")
      (node (ref "C126") (pin "1") (pinfunction "1_1") (pintype "passive"))
      (node (ref "C127") (pin "1") (pinfunction "1_1") (pintype "passive"))
      (node (ref "C18") (pin "1") (pinfunction "1_1") (pintype "passive"))
      (node (ref "C19") (pin "1") (pinfunction "1_1") (pintype "passive"))
      (node (ref "C20") (pin "1") (pinfunction "1_1") (pintype "passive"))
      (node (ref "C21") (pin "2") (pinfunction "2_2") (pintype "passive"))
      (node (ref "C24") (pin "2") (pinfunction "2_2") (pintype "passive"))
      (node (ref "C27") (pin "1") (pinfunction "1_1") (pintype "passive"))
      (node (ref "J15") (pin "P2") (pinfunction "PWR_P2") (pintype "passive"))
      (node (ref "R29") (pin "1") (pinfunction "1_1") (pintype "passive"))
      (node (ref "R30") (pin "2") (pinfunction "2_2") (pintype "passive"))
      (node (ref "R4") (pin "2") (pinfunction "2_2") (pintype "passive"))
      (node (ref "U3") (pin "1") (pinfunction "IN_1") (pintype "passive"))
      (node (ref "U3") (pin "3") (pinfunction "EN_3") (pintype "passive"))
      (node (ref "U4") (pin "12") (pinfunction "VIN2_12") (pintype "passive"))
      (node (ref "U4") (pin "13") (pinfunction "VIN3_13") (pintype "passive"))
      (node (ref "U4") (pin "28") (pinfunction "VIN1_28") (pintype "passive"))
      (node (ref "U4") (pin "5") (pinfunction "VINQ_5") (pintype "passive"))
      (node (ref "U5") (pin "1") (pinfunction "IN_1") (pintype "passive"))
      (node (ref "U5") (pin "3") (pinfunction "EN_3") (pintype "passive"))
    )
    (net (code "30") (name "unconnected-(U3-NC-Pad4)") (class "Default")
      (node (ref "U3") (pin "4") (pinfunction "NC_4") (pintype "passive+no_connect"))
    )
    (net (code "31") (name "unconnected-(U5-NC-Pad4)") (class "Default")
      (node (ref "U5") (pin "4") (pinfunction "NC_4") (pintype "passive+no_connect"))
    )
  )
)
